# Grove_-_3-Axis_Analog_Accelerometer_v1_1.net
KiCad netlist of a schematic drawn in EAGLE
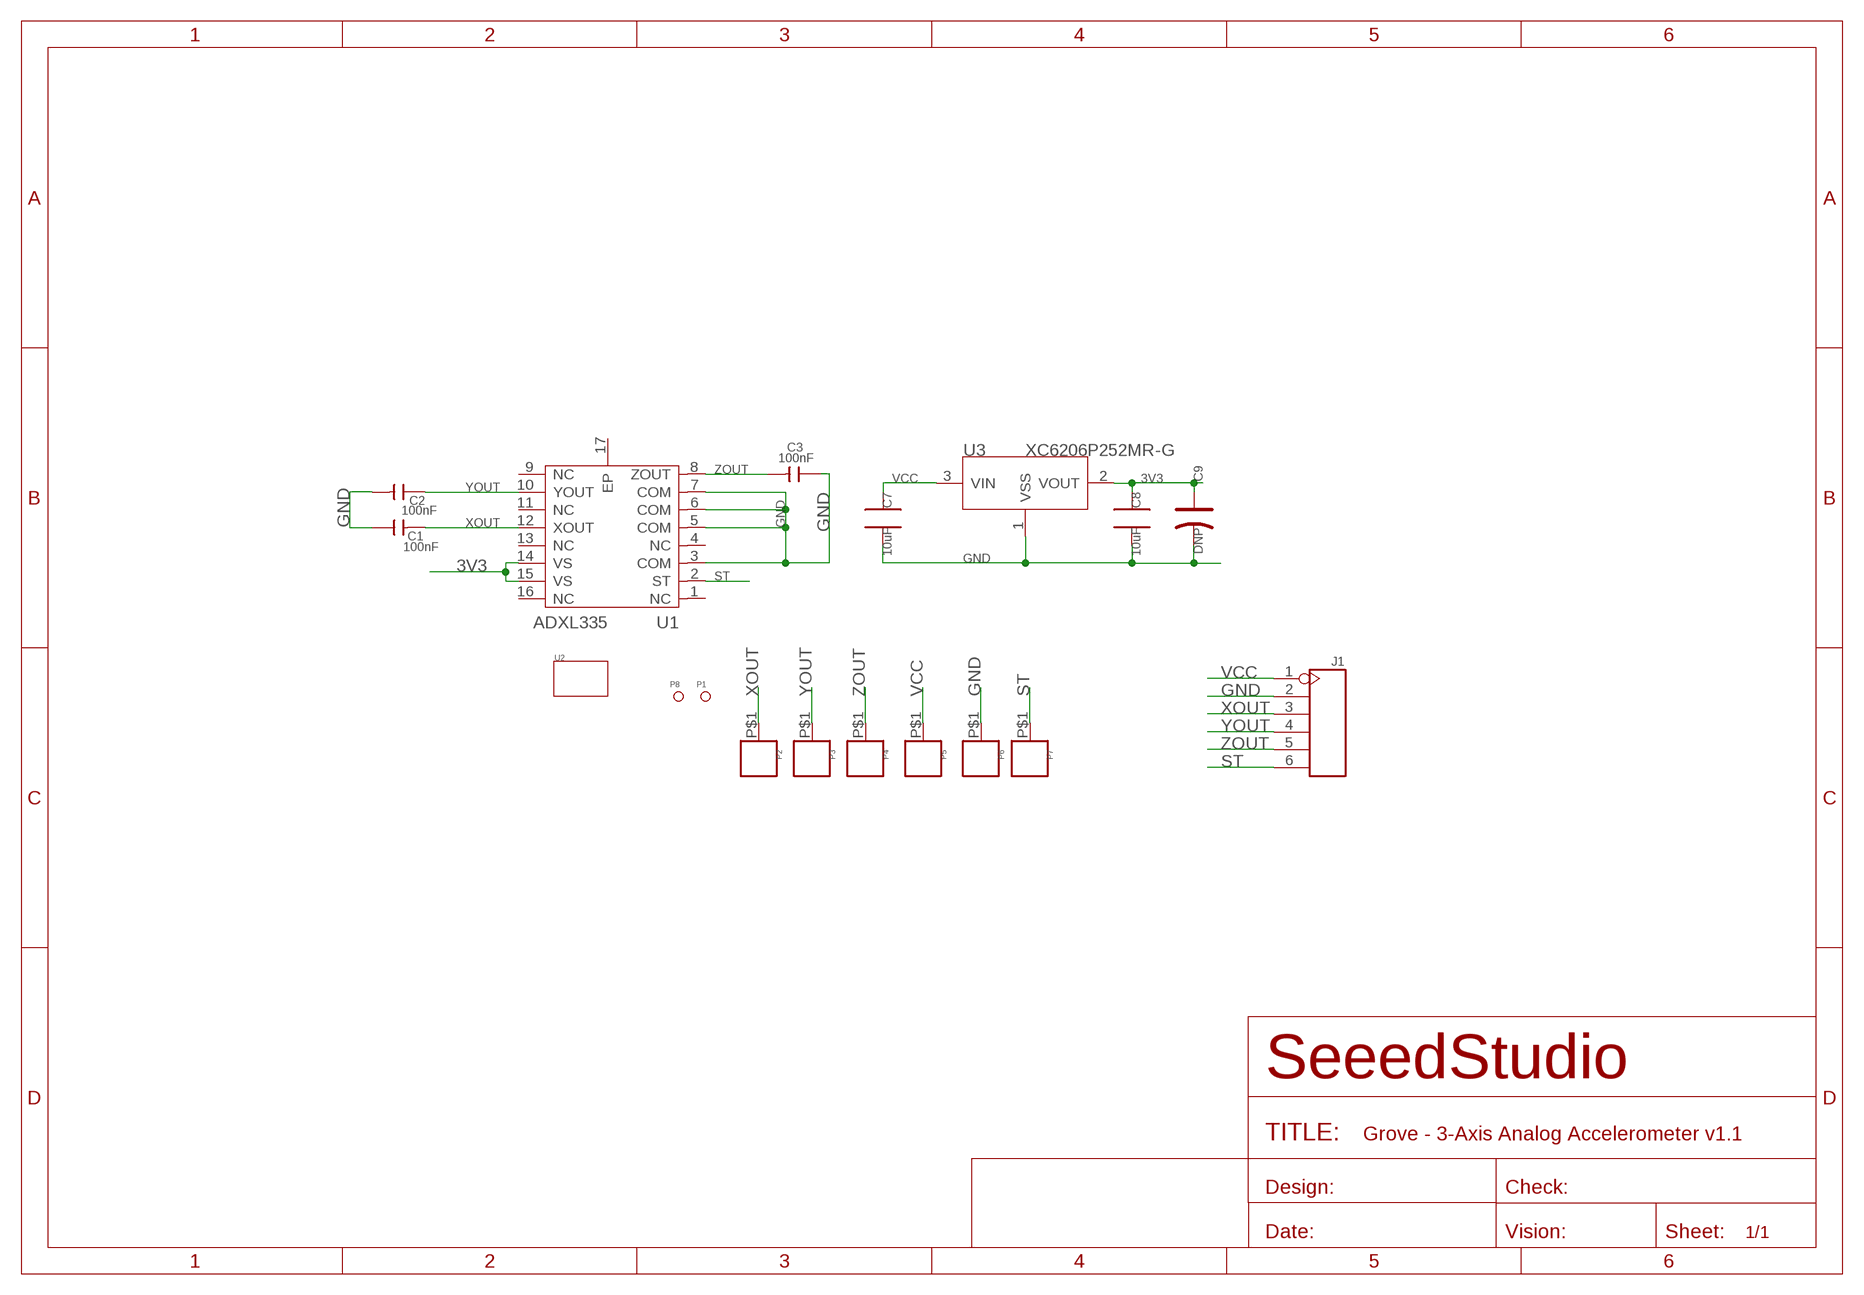
[diagram p0: schematic, sheet 1]

(export (version "E")
  (design (tool "Eeschema 10.0.6"))
  (components
    (comp (ref "C1")
      (value "100nF")
      (footprint "eagle-import:C0603")
      (libsource (lib "eagle-import") (part "C-0603"))
    )
    (comp (ref "C2")
      (value "100nF")
      (footprint "eagle-import:C0603")
      (libsource (lib "eagle-import") (part "C-0603"))
    )
    (comp (ref "C3")
      (value "100nF")
      (footprint "eagle-import:C0603")
      (libsource (lib "eagle-import") (part "C-0603"))
    )
    (comp (ref "C7")
      (value "10uF")
      (footprint "eagle-import:0805_S")
      (libsource (lib "eagle-import") (part "C0805_S"))
    )
    (comp (ref "C8")
      (value "10uF")
      (footprint "eagle-import:0805_S")
      (libsource (lib "eagle-import") (part "C0805_S"))
    )
    (comp (ref "C9")
      (value "DNP")
      (footprint "eagle-import:AVX-A")
      (libsource (lib "eagle-import") (part "CAP-AVX-A"))
    )
    (comp (ref "J1")
      (value "HEADER-6P-60/35MIL")
      (footprint "eagle-import:6P-2.54-60_35MIL")
      (libsource (lib "eagle-import") (part "HEADER-6P-60/35MIL"))
    )
    (comp (ref "P1")
      (value "PAD-MARK")
      (footprint "eagle-import:ROUND-MARK-1.0")
      (fields (field (name "PARTNO") "DNP"))
      (libsource (lib "eagle-import") (part "PAD-MARK"))
    )
    (comp (ref "P2")
      (value "PAD'1X2MM'")
      (footprint "eagle-import:1P-1X2")
      (libsource (lib "eagle-import") (part "PAD'1X2MM'"))
    )
    (comp (ref "P3")
      (value "PAD'1X2MM'")
      (footprint "eagle-import:1P-1X2")
      (libsource (lib "eagle-import") (part "PAD'1X2MM'"))
    )
    (comp (ref "P4")
      (value "PAD'1X2MM'")
      (footprint "eagle-import:1P-1X2")
      (libsource (lib "eagle-import") (part "PAD'1X2MM'"))
    )
    (comp (ref "P5")
      (value "PAD'1X2MM'")
      (footprint "eagle-import:1P-1X2")
      (libsource (lib "eagle-import") (part "PAD'1X2MM'"))
    )
    (comp (ref "P6")
      (value "PAD'1X2MM'")
      (footprint "eagle-import:1P-1X2")
      (libsource (lib "eagle-import") (part "PAD'1X2MM'"))
    )
    (comp (ref "P7")
      (value "PAD'1X2MM'")
      (footprint "eagle-import:1P-1X2")
      (libsource (lib "eagle-import") (part "PAD'1X2MM'"))
    )
    (comp (ref "P8")
      (value "PAD-MARK")
      (footprint "eagle-import:ROUND-MARK-1.0")
      (fields (field (name "PARTNO") "DNP") (field (name "PARTNO_1") "DNP"))
      (libsource (lib "eagle-import") (part "PAD-MARK"))
    )
    (comp (ref "U1")
      (value "ADXL335")
      (footprint "eagle-import:LFCSP16-4X4")
      (libsource (lib "eagle-import") (part "ADXL335"))
    )
    (comp (ref "U2")
      (value "TWIG-1U")
      (footprint "eagle-import:1U-DIM-W_-DRILL")
      (libsource (lib "eagle-import") (part "TWIG-1U"))
    )
    (comp (ref "U3")
      (value "XC6206P252MR-G")
      (footprint "eagle-import:SOT23")
      (libsource (lib "eagle-import") (part "XC6206MR"))
    )
  )
  (nets
    (net (code "1") (name "/3V3") (class "Default")
      (node (ref "C8") (pin "1") (pinfunction "1_1") (pintype "bidirectional"))
      (node (ref "C9") (pin "+") (pinfunction "+_+") (pintype "passive"))
      (node (ref "U1") (pin "14") (pinfunction "VS_14") (pintype "bidirectional"))
      (node (ref "U1") (pin "15") (pinfunction "VS_15") (pintype "bidirectional"))
      (node (ref "U3") (pin "2") (pinfunction "VOUT_2") (pintype "output"))
    )
    (net (code "2") (name "/GND") (class "Default")
      (node (ref "C1") (pin "1") (pinfunction "1_1") (pintype "passive"))
      (node (ref "C2") (pin "2") (pinfunction "2_2") (pintype "passive"))
      (node (ref "C3") (pin "1") (pinfunction "1_1") (pintype "passive"))
      (node (ref "C7") (pin "2") (pinfunction "2_2") (pintype "bidirectional"))
      (node (ref "C8") (pin "2") (pinfunction "2_2") (pintype "bidirectional"))
      (node (ref "C9") (pin "-") (pinfunction "-_-") (pintype "passive"))
      (node (ref "J1") (pin "2") (pinfunction "2_2") (pintype "bidirectional"))
      (node (ref "P6") (pin "P$1") (pinfunction "P$1_P$1") (pintype "bidirectional"))
      (node (ref "U1") (pin "3") (pinfunction "COM_3") (pintype "bidirectional"))
      (node (ref "U1") (pin "5") (pinfunction "COM_5") (pintype "bidirectional"))
      (node (ref "U1") (pin "6") (pinfunction "COM_6") (pintype "bidirectional"))
      (node (ref "U1") (pin "7") (pinfunction "COM_7") (pintype "bidirectional"))
      (node (ref "U3") (pin "1") (pinfunction "VSS_1") (pintype "power_in"))
    )
    (net (code "3") (name "/ST") (class "Default")
      (node (ref "J1") (pin "6") (pinfunction "6_6") (pintype "bidirectional"))
      (node (ref "P7") (pin "P$1") (pinfunction "P$1_P$1") (pintype "bidirectional"))
      (node (ref "U1") (pin "2") (pinfunction "ST_2") (pintype "bidirectional"))
    )
    (net (code "4") (name "/VCC") (class "Default")
      (node (ref "C7") (pin "1") (pinfunction "1_1") (pintype "bidirectional"))
      (node (ref "J1") (pin "1") (pinfunction "1_1") (pintype "bidirectional"))
      (node (ref "P5") (pin "P$1") (pinfunction "P$1_P$1") (pintype "bidirectional"))
      (node (ref "U3") (pin "3") (pinfunction "VIN_3") (pintype "input"))
    )
    (net (code "5") (name "/XOUT") (class "Default")
      (node (ref "C1") (pin "2") (pinfunction "2_2") (pintype "passive"))
      (node (ref "J1") (pin "3") (pinfunction "3_3") (pintype "bidirectional"))
      (node (ref "P2") (pin "P$1") (pinfunction "P$1_P$1") (pintype "bidirectional"))
      (node (ref "U1") (pin "12") (pinfunction "XOUT_12") (pintype "bidirectional"))
    )
    (net (code "6") (name "/YOUT") (class "Default")
      (node (ref "C2") (pin "1") (pinfunction "1_1") (pintype "passive"))
      (node (ref "J1") (pin "4") (pinfunction "4_4") (pintype "bidirectional"))
      (node (ref "P3") (pin "P$1") (pinfunction "P$1_P$1") (pintype "bidirectional"))
      (node (ref "U1") (pin "10") (pinfunction "YOUT_10") (pintype "bidirectional"))
    )
    (net (code "7") (name "/ZOUT") (class "Default")
      (node (ref "C3") (pin "2") (pinfunction "2_2") (pintype "passive"))
      (node (ref "J1") (pin "5") (pinfunction "5_5") (pintype "bidirectional"))
      (node (ref "P4") (pin "P$1") (pinfunction "P$1_P$1") (pintype "bidirectional"))
      (node (ref "U1") (pin "8") (pinfunction "ZOUT_8") (pintype "bidirectional"))
    )
    (net (code "8") (name "unconnected-(U1-EP-Pad17)") (class "Default")
      (node (ref "U1") (pin "17") (pinfunction "EP_17") (pintype "bidirectional"))
    )
    (net (code "9") (name "unconnected-(U1-NC-Pad1)") (class "Default")
      (node (ref "U1") (pin "1") (pinfunction "NC_1") (pintype "no_connect"))
    )
    (net (code "10") (name "unconnected-(U1-NC-Pad4)") (class "Default")
      (node (ref "U1") (pin "4") (pinfunction "NC_4") (pintype "no_connect"))
    )
    (net (code "11") (name "unconnected-(U1-NC-Pad9)") (class "Default")
      (node (ref "U1") (pin "9") (pinfunction "NC_9") (pintype "no_connect"))
    )
    (net (code "12") (name "unconnected-(U1-NC-Pad11)") (class "Default")
      (node (ref "U1") (pin "11") (pinfunction "NC_11") (pintype "no_connect"))
    )
    (net (code "13") (name "unconnected-(U1-NC-Pad13)") (class "Default")
      (node (ref "U1") (pin "13") (pinfunction "NC_13") (pintype "no_connect"))
    )
    (net (code "14") (name "unconnected-(U1-NC-Pad16)") (class "Default")
      (node (ref "U1") (pin "16") (pinfunction "NC_16") (pintype "no_connect"))
    )
  )
)
